# probe_v2.net
KiCad netlist of a schematic drawn in EAGLE
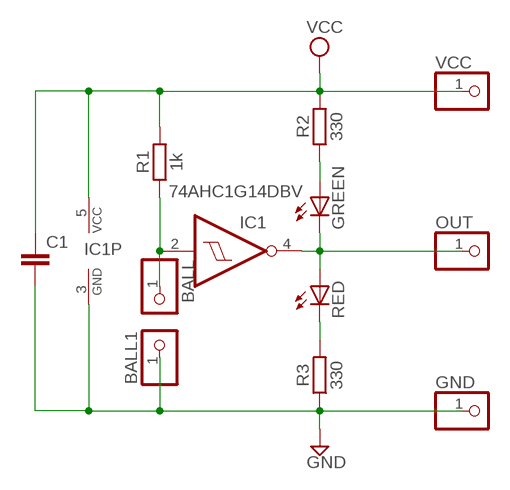
[diagram p0: schematic, sheet 1]

(export (version "E")
  (design (tool "Eeschema 10.0.6"))
  (components
    (comp (ref "BALL")
      (value "PINHD-1X1")
      (footprint "eagle-import:1X01")
      (libsource (lib "eagle-import") (part "PINHD-1X1"))
    )
    (comp (ref "BALL1")
      (value "PINHD-1X1")
      (footprint "eagle-import:1X01")
      (libsource (lib "eagle-import") (part "PINHD-1X1"))
    )
    (comp (ref "C1")
      (value "C-EUC0805")
      (footprint "eagle-import:C0805")
      (libsource (lib "eagle-import") (part "C-EUC0805"))
    )
    (comp (ref "GND")
      (value "PINHD-1X1")
      (footprint "eagle-import:1X01")
      (libsource (lib "eagle-import") (part "PINHD-1X1"))
    )
    (comp (ref "GREEN")
      (value "LEDCHIPLED_1206")
      (footprint "eagle-import:CHIPLED_1206")
      (libsource (lib "eagle-import") (part "LEDCHIPLED_1206"))
    )
    (comp (ref "IC1")
      (value "74AHC1G14DBV")
      (footprint "eagle-import:SOT23-5")
      (libsource (lib "eagle-import") (part "741G14DBVAHC"))
    )
    (comp (ref "OUT")
      (value "PINHD-1X1")
      (footprint "eagle-import:1X01")
      (libsource (lib "eagle-import") (part "PINHD-1X1"))
    )
    (comp (ref "R1")
      (value "1k")
      (footprint "eagle-import:R0805")
      (libsource (lib "eagle-import") (part "R-EU_R0805"))
    )
    (comp (ref "R2")
      (value "330")
      (footprint "eagle-import:M1206")
      (libsource (lib "eagle-import") (part "R-EU_M1206"))
    )
    (comp (ref "R3")
      (value "330")
      (footprint "eagle-import:M1206")
      (libsource (lib "eagle-import") (part "R-EU_M1206"))
    )
    (comp (ref "RED")
      (value "LEDCHIPLED_1206")
      (footprint "eagle-import:CHIPLED_1206")
      (libsource (lib "eagle-import") (part "LEDCHIPLED_1206"))
    )
    (comp (ref "VCC")
      (value "PINHD-1X1")
      (footprint "eagle-import:1X01")
      (libsource (lib "eagle-import") (part "PINHD-1X1"))
    )
  )
  (nets
    (net (code "1") (name "GND") (class "Default")
      (node (ref "BALL1") (pin "1") (pinfunction "1_1") (pintype "passive"))
      (node (ref "C1") (pin "2") (pinfunction "2_2") (pintype "passive"))
      (node (ref "GND") (pin "1") (pinfunction "1_1") (pintype "passive"))
      (node (ref "IC1") (pin "3") (pinfunction "GND_3") (pintype "power_in"))
      (node (ref "R3") (pin "1") (pinfunction "1_1") (pintype "passive"))
    )
    (net (code "2") (name "Net-(GREEN-PadA)") (class "Default")
      (node (ref "GREEN") (pin "A") (pinfunction "A_A") (pintype "passive"))
      (node (ref "R2") (pin "1") (pinfunction "1_1") (pintype "passive"))
    )
    (net (code "3") (name "Net-(IC1A-I)") (class "Default")
      (node (ref "BALL") (pin "1") (pinfunction "1_1") (pintype "passive"))
      (node (ref "IC1") (pin "2") (pinfunction "I_2") (pintype "input"))
      (node (ref "R1") (pin "1") (pinfunction "1_1") (pintype "passive"))
    )
    (net (code "4") (name "Net-(IC1A-O)") (class "Default")
      (node (ref "GREEN") (pin "C") (pinfunction "C_C") (pintype "passive"))
      (node (ref "IC1") (pin "4") (pinfunction "O_4") (pintype "output"))
      (node (ref "OUT") (pin "1") (pinfunction "1_1") (pintype "passive"))
      (node (ref "RED") (pin "A") (pinfunction "A_A") (pintype "passive"))
    )
    (net (code "5") (name "Net-(R3-Pad2)") (class "Default")
      (node (ref "R3") (pin "2") (pinfunction "2_2") (pintype "passive"))
      (node (ref "RED") (pin "C") (pinfunction "C_C") (pintype "passive"))
    )
    (net (code "6") (name "VCC") (class "Default")
      (node (ref "C1") (pin "1") (pinfunction "1_1") (pintype "passive"))
      (node (ref "IC1") (pin "5") (pinfunction "VCC_5") (pintype "power_in"))
      (node (ref "R1") (pin "2") (pinfunction "2_2") (pintype "passive"))
      (node (ref "R2") (pin "2") (pinfunction "2_2") (pintype "passive"))
      (node (ref "VCC") (pin "1") (pinfunction "1_1") (pintype "passive"))
    )
  )
)
